# 6_AnalogChannels_5_6_7_8.net
KiCad netlist of a schematic drawn in Altium Designer
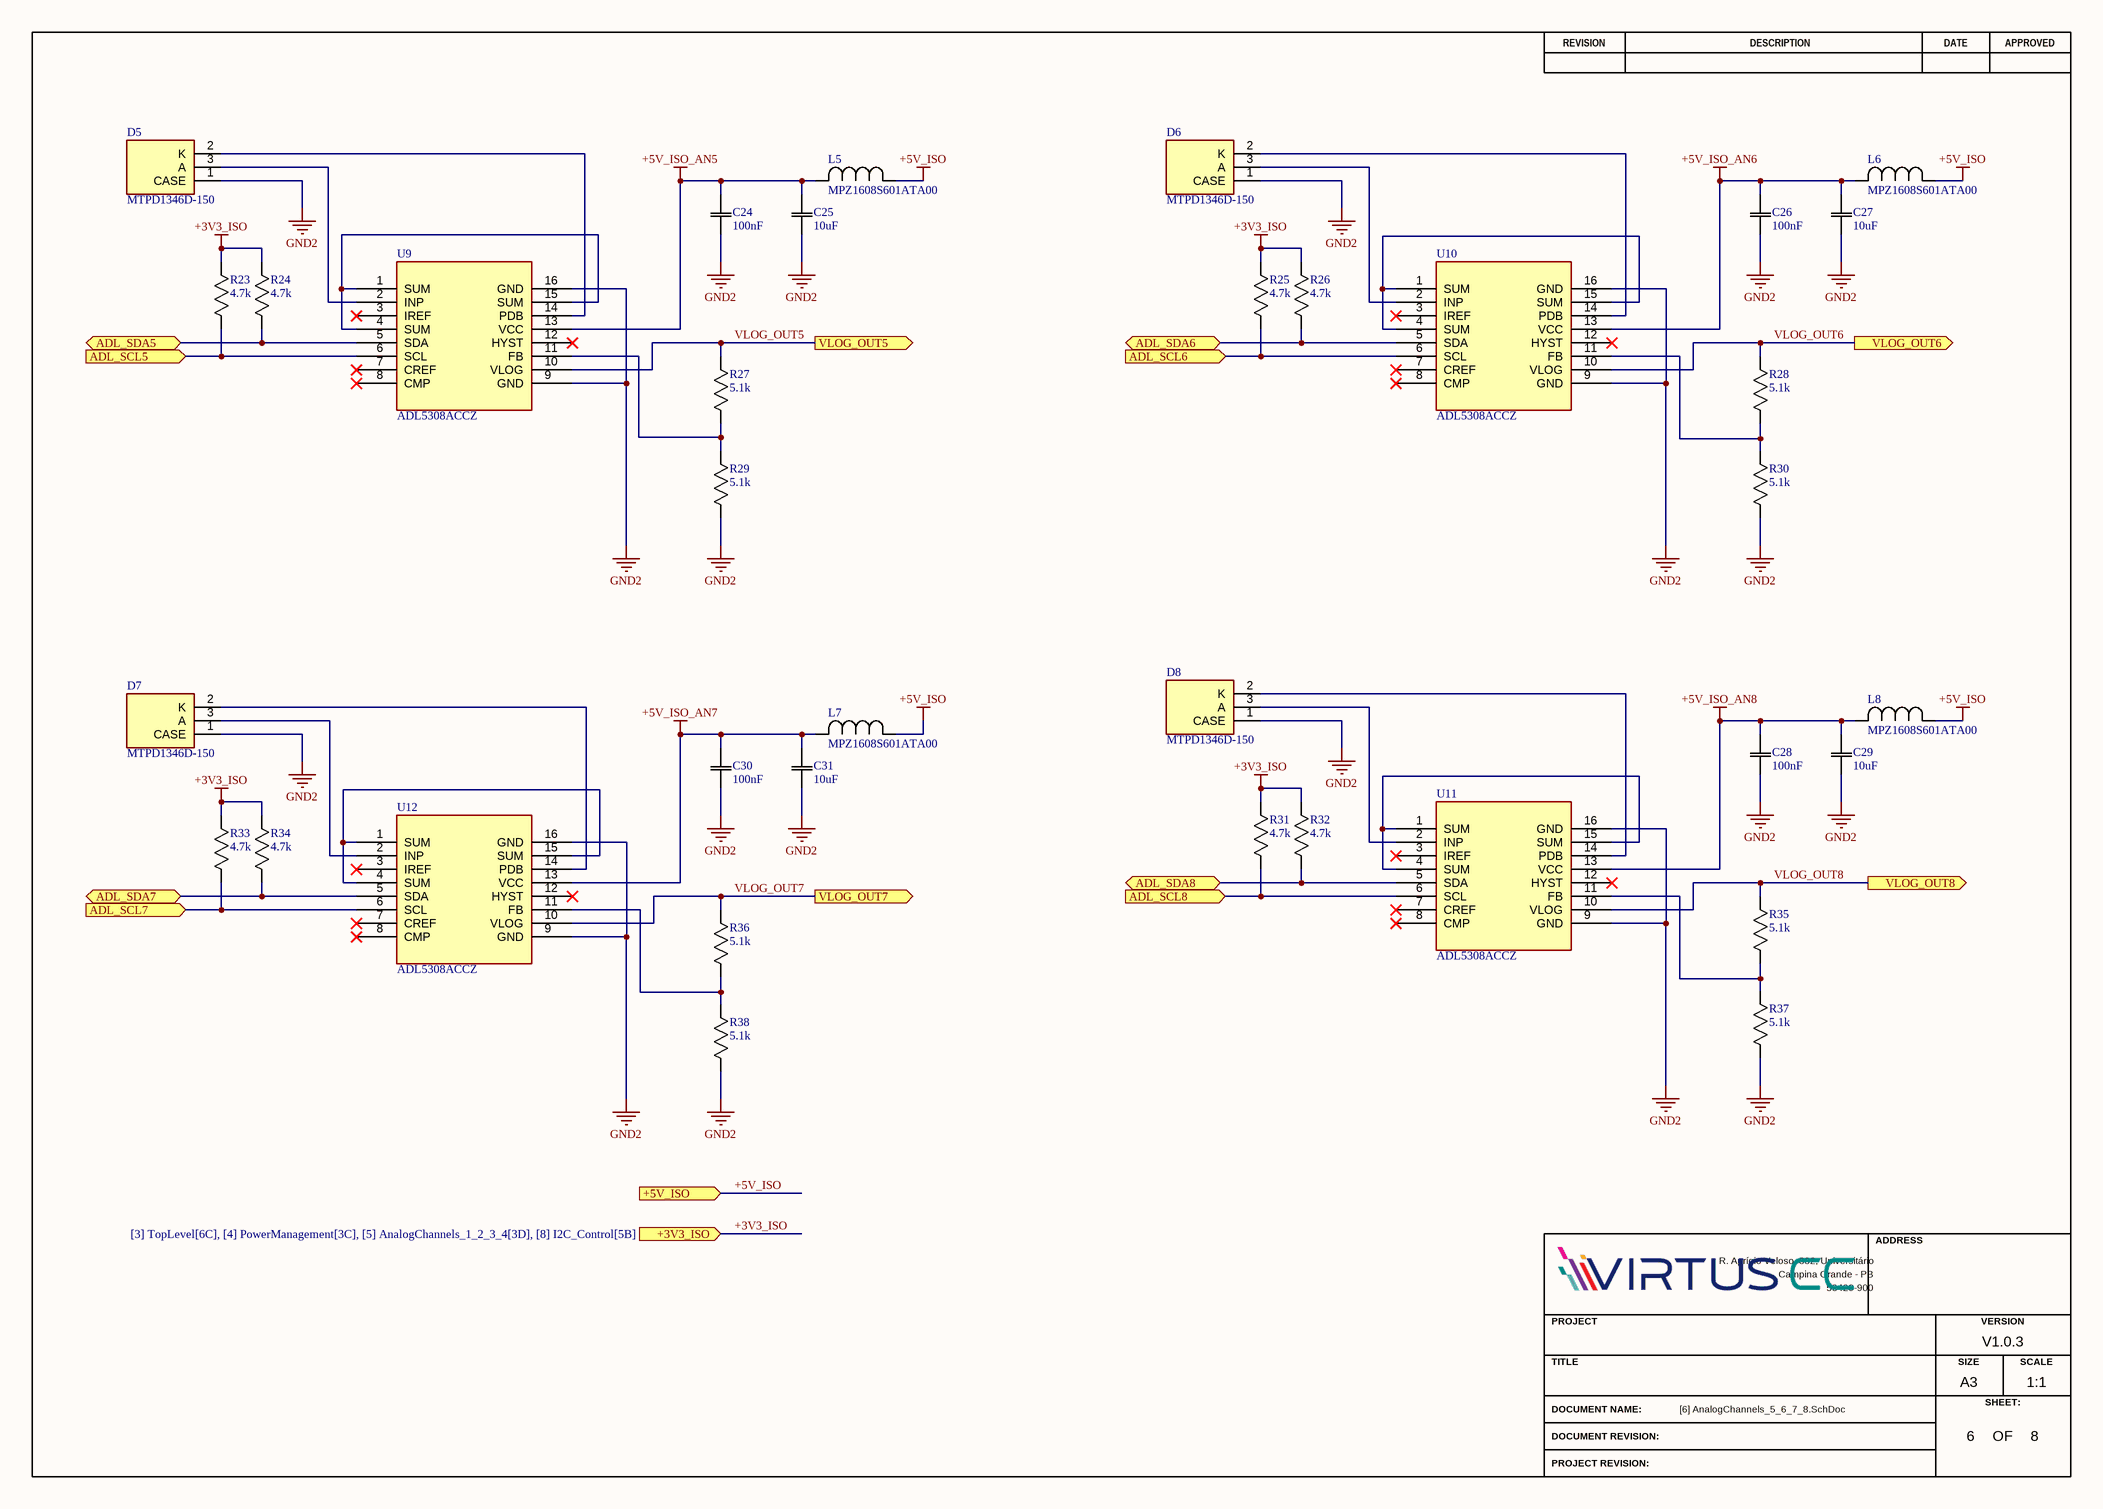
[diagram p0: [6] AnalogChannels_5_6_7_8.SchDoc]

(export (version "E")
  (design (tool "Eeschema 10.0.6"))
  (components
    (comp (ref "C24")
      (value "100nF")
      (footprint "CAPC1005X40N")
      (description "0.1 µF ±10% 50V Ceramic Capacitor X7R 0402 (1005 Metric)")
      (fields
        (field (name "MANUFACTURER_PART_NUMBER") "GCM155R71H104KE02D")
        (field (name "COPYRIGHT") "Copyright (C) 2026 Ultra Librarian. All rights reserved.")
      )
      (libsource (lib "PCEIOT") (part "GCM155R71H104KE02D"))
    )
    (comp (ref "C25")
      (value "10uF")
      (footprint "CAPC1005X40N")
      (description "10 µF ±20% 10V Ceramic Capacitor X5R 0402 (1005 Metric)")
      (fields
        (field (name "MANUFACTURER_PART_NUMBER") "GRT155R61A106ME13D")
        (field (name "COPYRIGHT") "Copyright (C) 2026 Ultra Librarian. All rights reserved.")
      )
      (libsource (lib "PCEIOT") (part "GRT155R61A106ME13D"))
    )
    (comp (ref "C26")
      (value "100nF")
      (footprint "CAPC1005X40N")
      (description "0.1 µF ±10% 50V Ceramic Capacitor X7R 0402 (1005 Metric)")
      (fields
        (field (name "MANUFACTURER_PART_NUMBER") "GCM155R71H104KE02D")
        (field (name "COPYRIGHT") "Copyright (C) 2026 Ultra Librarian. All rights reserved.")
      )
      (libsource (lib "PCEIOT") (part "GCM155R71H104KE02D"))
    )
    (comp (ref "C27")
      (value "10uF")
      (footprint "CAPC1005X40N")
      (description "10 µF ±20% 10V Ceramic Capacitor X5R 0402 (1005 Metric)")
      (fields
        (field (name "MANUFACTURER_PART_NUMBER") "GRT155R61A106ME13D")
        (field (name "COPYRIGHT") "Copyright (C) 2026 Ultra Librarian. All rights reserved.")
      )
      (libsource (lib "PCEIOT") (part "GRT155R61A106ME13D"))
    )
    (comp (ref "C28")
      (value "100nF")
      (footprint "CAPC1005X40N")
      (description "0.1 µF ±10% 50V Ceramic Capacitor X7R 0402 (1005 Metric)")
      (fields
        (field (name "MANUFACTURER_PART_NUMBER") "GCM155R71H104KE02D")
        (field (name "COPYRIGHT") "Copyright (C) 2026 Ultra Librarian. All rights reserved.")
      )
      (libsource (lib "PCEIOT") (part "GCM155R71H104KE02D"))
    )
    (comp (ref "C29")
      (value "10uF")
      (footprint "CAPC1005X40N")
      (description "10 µF ±20% 10V Ceramic Capacitor X5R 0402 (1005 Metric)")
      (fields
        (field (name "MANUFACTURER_PART_NUMBER") "GRT155R61A106ME13D")
        (field (name "COPYRIGHT") "Copyright (C) 2026 Ultra Librarian. All rights reserved.")
      )
      (libsource (lib "PCEIOT") (part "GRT155R61A106ME13D"))
    )
    (comp (ref "C30")
      (value "100nF")
      (footprint "CAPC1005X40N")
      (description "0.1 µF ±10% 50V Ceramic Capacitor X7R 0402 (1005 Metric)")
      (fields
        (field (name "MANUFACTURER_PART_NUMBER") "GCM155R71H104KE02D")
        (field (name "COPYRIGHT") "Copyright (C) 2026 Ultra Librarian. All rights reserved.")
      )
      (libsource (lib "PCEIOT") (part "GCM155R71H104KE02D"))
    )
    (comp (ref "C31")
      (value "10uF")
      (footprint "CAPC1005X40N")
      (description "10 µF ±20% 10V Ceramic Capacitor X5R 0402 (1005 Metric)")
      (fields
        (field (name "MANUFACTURER_PART_NUMBER") "GRT155R61A106ME13D")
        (field (name "COPYRIGHT") "Copyright (C) 2026 Ultra Librarian. All rights reserved.")
      )
      (libsource (lib "PCEIOT") (part "GRT155R61A106ME13D"))
    )
    (comp (ref "D5")
      (value "MTPD1346D-150")
      (footprint "TO127P540X1680-3N")
      (description "Photodiode 1300nm TO-46-3 Lens Top Metal Can")
      (libsource (lib "PCEIOT") (part "MTPD1346D-150"))
    )
    (comp (ref "D6")
      (value "MTPD1346D-150")
      (footprint "TO127P540X1680-3N")
      (description "Photodiode 1300nm TO-46-3 Lens Top Metal Can")
      (libsource (lib "PCEIOT") (part "MTPD1346D-150"))
    )
    (comp (ref "D7")
      (value "MTPD1346D-150")
      (footprint "TO127P540X1680-3N")
      (description "Photodiode 1300nm TO-46-3 Lens Top Metal Can")
      (libsource (lib "PCEIOT") (part "MTPD1346D-150"))
    )
    (comp (ref "D8")
      (value "MTPD1346D-150")
      (footprint "TO127P540X1680-3N")
      (description "Photodiode 1300nm TO-46-3 Lens Top Metal Can")
      (libsource (lib "PCEIOT") (part "MTPD1346D-150"))
    )
    (comp (ref "L5")
      (value "MPZ1608S601ATA00")
      (footprint "INDC1608X06N")
      (description "INDUCTOR; SMT (0603); FERRITE-BEAD; 600; TOL=+/-25%; 1A; -55 DEGC TO +125 DEGC")
      (fields (field (name "COPYRIGHT") "Copyright (C) 2026 Ultra Librarian. All rights reserved."))
      (libsource (lib "PCEIOT") (part "MPZ1608S601ATA00"))
    )
    (comp (ref "L6")
      (value "MPZ1608S601ATA00")
      (footprint "INDC1608X06N")
      (description "INDUCTOR; SMT (0603); FERRITE-BEAD; 600; TOL=+/-25%; 1A; -55 DEGC TO +125 DEGC")
      (fields (field (name "COPYRIGHT") "Copyright (C) 2026 Ultra Librarian. All rights reserved."))
      (libsource (lib "PCEIOT") (part "MPZ1608S601ATA00"))
    )
    (comp (ref "L7")
      (value "MPZ1608S601ATA00")
      (footprint "INDC1608X06N")
      (description "INDUCTOR; SMT (0603); FERRITE-BEAD; 600; TOL=+/-25%; 1A; -55 DEGC TO +125 DEGC")
      (fields (field (name "COPYRIGHT") "Copyright (C) 2026 Ultra Librarian. All rights reserved."))
      (libsource (lib "PCEIOT") (part "MPZ1608S601ATA00"))
    )
    (comp (ref "L8")
      (value "MPZ1608S601ATA00")
      (footprint "INDC1608X06N")
      (description "INDUCTOR; SMT (0603); FERRITE-BEAD; 600; TOL=+/-25%; 1A; -55 DEGC TO +125 DEGC")
      (fields (field (name "COPYRIGHT") "Copyright (C) 2026 Ultra Librarian. All rights reserved."))
      (libsource (lib "PCEIOT") (part "MPZ1608S601ATA00"))
    )
    (comp (ref "R23")
      (value "4.7k")
      (footprint "RESC1005X40N")
      (description "4.7 kOhms ±1% 0.063W, 1/16W Chip Resistor 0402 (1005 Metric) Moisture Resistant Thick Film")
      (fields
        (field (name "MANUFACTURER_PART_NUMBER") "RC0402FR-074K7L")
        (field (name "COPYRIGHT") "Copyright (C) 2025 Ultra Librarian. All rights reserved.")
      )
      (libsource (lib "PCEIOT") (part "RC0402FR-074K7L"))
    )
    (comp (ref "R24")
      (value "4.7k")
      (footprint "RESC1005X40N")
      (description "4.7 kOhms ±1% 0.063W, 1/16W Chip Resistor 0402 (1005 Metric) Moisture Resistant Thick Film")
      (fields
        (field (name "MANUFACTURER_PART_NUMBER") "RC0402FR-074K7L")
        (field (name "COPYRIGHT") "Copyright (C) 2025 Ultra Librarian. All rights reserved.")
      )
      (libsource (lib "PCEIOT") (part "RC0402FR-074K7L"))
    )
    (comp (ref "R25")
      (value "4.7k")
      (footprint "RESC1005X40N")
      (description "4.7 kOhms ±1% 0.063W, 1/16W Chip Resistor 0402 (1005 Metric) Moisture Resistant Thick Film")
      (fields
        (field (name "MANUFACTURER_PART_NUMBER") "RC0402FR-074K7L")
        (field (name "COPYRIGHT") "Copyright (C) 2025 Ultra Librarian. All rights reserved.")
      )
      (libsource (lib "PCEIOT") (part "RC0402FR-074K7L"))
    )
    (comp (ref "R26")
      (value "4.7k")
      (footprint "RESC1005X40N")
      (description "4.7 kOhms ±1% 0.063W, 1/16W Chip Resistor 0402 (1005 Metric) Moisture Resistant Thick Film")
      (fields
        (field (name "MANUFACTURER_PART_NUMBER") "RC0402FR-074K7L")
        (field (name "COPYRIGHT") "Copyright (C) 2025 Ultra Librarian. All rights reserved.")
      )
      (libsource (lib "PCEIOT") (part "RC0402FR-074K7L"))
    )
    (comp (ref "R27")
      (value "5.1k")
      (footprint "RESC1005X40N")
      (description "5.1 kOhms ±1% 0.063W, 1/16W Chip Resistor 0402 (1005 Metric) Moisture Resistant Thick Film")
      (fields
        (field (name "MANUFACTURER_PART_NUMBER") "RC0402FR-075K1L")
        (field (name "COPYRIGHT") "Copyright (C) 2025 Ultra Librarian. All rights reserved.")
      )
      (libsource (lib "PCEIOT") (part "RC0402FR-075K1L"))
    )
    (comp (ref "R28")
      (value "5.1k")
      (footprint "RESC1005X40N")
      (description "5.1 kOhms ±1% 0.063W, 1/16W Chip Resistor 0402 (1005 Metric) Moisture Resistant Thick Film")
      (fields
        (field (name "MANUFACTURER_PART_NUMBER") "RC0402FR-075K1L")
        (field (name "COPYRIGHT") "Copyright (C) 2025 Ultra Librarian. All rights reserved.")
      )
      (libsource (lib "PCEIOT") (part "RC0402FR-075K1L"))
    )
    (comp (ref "R29")
      (value "5.1k")
      (footprint "RESC1005X40N")
      (description "5.1 kOhms ±1% 0.063W, 1/16W Chip Resistor 0402 (1005 Metric) Moisture Resistant Thick Film")
      (fields
        (field (name "MANUFACTURER_PART_NUMBER") "RC0402FR-075K1L")
        (field (name "COPYRIGHT") "Copyright (C) 2025 Ultra Librarian. All rights reserved.")
      )
      (libsource (lib "PCEIOT") (part "RC0402FR-075K1L"))
    )
    (comp (ref "R30")
      (value "5.1k")
      (footprint "RESC1005X40N")
      (description "5.1 kOhms ±1% 0.063W, 1/16W Chip Resistor 0402 (1005 Metric) Moisture Resistant Thick Film")
      (fields
        (field (name "MANUFACTURER_PART_NUMBER") "RC0402FR-075K1L")
        (field (name "COPYRIGHT") "Copyright (C) 2025 Ultra Librarian. All rights reserved.")
      )
      (libsource (lib "PCEIOT") (part "RC0402FR-075K1L"))
    )
    (comp (ref "R31")
      (value "4.7k")
      (footprint "RESC1005X40N")
      (description "4.7 kOhms ±1% 0.063W, 1/16W Chip Resistor 0402 (1005 Metric) Moisture Resistant Thick Film")
      (fields
        (field (name "MANUFACTURER_PART_NUMBER") "RC0402FR-074K7L")
        (field (name "COPYRIGHT") "Copyright (C) 2025 Ultra Librarian. All rights reserved.")
      )
      (libsource (lib "PCEIOT") (part "RC0402FR-074K7L"))
    )
    (comp (ref "R32")
      (value "4.7k")
      (footprint "RESC1005X40N")
      (description "4.7 kOhms ±1% 0.063W, 1/16W Chip Resistor 0402 (1005 Metric) Moisture Resistant Thick Film")
      (fields
        (field (name "MANUFACTURER_PART_NUMBER") "RC0402FR-074K7L")
        (field (name "COPYRIGHT") "Copyright (C) 2025 Ultra Librarian. All rights reserved.")
      )
      (libsource (lib "PCEIOT") (part "RC0402FR-074K7L"))
    )
    (comp (ref "R33")
      (value "4.7k")
      (footprint "RESC1005X40N")
      (description "4.7 kOhms ±1% 0.063W, 1/16W Chip Resistor 0402 (1005 Metric) Moisture Resistant Thick Film")
      (fields
        (field (name "MANUFACTURER_PART_NUMBER") "RC0402FR-074K7L")
        (field (name "COPYRIGHT") "Copyright (C) 2025 Ultra Librarian. All rights reserved.")
      )
      (libsource (lib "PCEIOT") (part "RC0402FR-074K7L"))
    )
    (comp (ref "R34")
      (value "4.7k")
      (footprint "RESC1005X40N")
      (description "4.7 kOhms ±1% 0.063W, 1/16W Chip Resistor 0402 (1005 Metric) Moisture Resistant Thick Film")
      (fields
        (field (name "MANUFACTURER_PART_NUMBER") "RC0402FR-074K7L")
        (field (name "COPYRIGHT") "Copyright (C) 2025 Ultra Librarian. All rights reserved.")
      )
      (libsource (lib "PCEIOT") (part "RC0402FR-074K7L"))
    )
    (comp (ref "R35")
      (value "5.1k")
      (footprint "RESC1005X40N")
      (description "5.1 kOhms ±1% 0.063W, 1/16W Chip Resistor 0402 (1005 Metric) Moisture Resistant Thick Film")
      (fields
        (field (name "MANUFACTURER_PART_NUMBER") "RC0402FR-075K1L")
        (field (name "COPYRIGHT") "Copyright (C) 2025 Ultra Librarian. All rights reserved.")
      )
      (libsource (lib "PCEIOT") (part "RC0402FR-075K1L"))
    )
    (comp (ref "R36")
      (value "5.1k")
      (footprint "RESC1005X40N")
      (description "5.1 kOhms ±1% 0.063W, 1/16W Chip Resistor 0402 (1005 Metric) Moisture Resistant Thick Film")
      (fields
        (field (name "MANUFACTURER_PART_NUMBER") "RC0402FR-075K1L")
        (field (name "COPYRIGHT") "Copyright (C) 2025 Ultra Librarian. All rights reserved.")
      )
      (libsource (lib "PCEIOT") (part "RC0402FR-075K1L"))
    )
    (comp (ref "R37")
      (value "5.1k")
      (footprint "RESC1005X40N")
      (description "5.1 kOhms ±1% 0.063W, 1/16W Chip Resistor 0402 (1005 Metric) Moisture Resistant Thick Film")
      (fields
        (field (name "MANUFACTURER_PART_NUMBER") "RC0402FR-075K1L")
        (field (name "COPYRIGHT") "Copyright (C) 2025 Ultra Librarian. All rights reserved.")
      )
      (libsource (lib "PCEIOT") (part "RC0402FR-075K1L"))
    )
    (comp (ref "R38")
      (value "5.1k")
      (footprint "RESC1005X40N")
      (description "5.1 kOhms ±1% 0.063W, 1/16W Chip Resistor 0402 (1005 Metric) Moisture Resistant Thick Film")
      (fields
        (field (name "MANUFACTURER_PART_NUMBER") "RC0402FR-075K1L")
        (field (name "COPYRIGHT") "Copyright (C) 2025 Ultra Librarian. All rights reserved.")
      )
      (libsource (lib "PCEIOT") (part "RC0402FR-075K1L"))
    )
    (comp (ref "U9")
      (value "ADL5308ACCZ")
      (footprint "CC-14-4_ADI")
      (description "Logarithmic Converter, 105Deg C, Lga-Ep Rohs Compliant: Yes ¦Analog Devices, Inc. ADL5308ACCZ")
      (libsource (lib "PCEIOT") (part "ADL5308ACCZ"))
    )
    (comp (ref "U10")
      (value "ADL5308ACCZ")
      (footprint "CC-14-4_ADI")
      (description "Logarithmic Converter, 105Deg C, Lga-Ep Rohs Compliant: Yes ¦Analog Devices, Inc. ADL5308ACCZ")
      (libsource (lib "PCEIOT") (part "ADL5308ACCZ"))
    )
    (comp (ref "U11")
      (value "ADL5308ACCZ")
      (footprint "CC-14-4_ADI")
      (description "Logarithmic Converter, 105Deg C, Lga-Ep Rohs Compliant: Yes ¦Analog Devices, Inc. ADL5308ACCZ")
      (libsource (lib "PCEIOT") (part "ADL5308ACCZ"))
    )
    (comp (ref "U12")
      (value "ADL5308ACCZ")
      (footprint "CC-14-4_ADI")
      (description "Logarithmic Converter, 105Deg C, Lga-Ep Rohs Compliant: Yes ¦Analog Devices, Inc. ADL5308ACCZ")
      (libsource (lib "PCEIOT") (part "ADL5308ACCZ"))
    )
  )
  (nets
    (net (code "1") (name "+3V3_ISO") (class "Default")
      (node (ref "R23") (pin "1") (pinfunction "1_1") (pintype "passive"))
      (node (ref "R24") (pin "1") (pinfunction "1_1") (pintype "passive"))
      (node (ref "R25") (pin "1") (pinfunction "1_1") (pintype "passive"))
      (node (ref "R26") (pin "1") (pinfunction "1_1") (pintype "passive"))
      (node (ref "R31") (pin "1") (pinfunction "1_1") (pintype "passive"))
      (node (ref "R32") (pin "1") (pinfunction "1_1") (pintype "passive"))
      (node (ref "R33") (pin "1") (pinfunction "1_1") (pintype "passive"))
      (node (ref "R34") (pin "1") (pinfunction "1_1") (pintype "passive"))
    )
    (net (code "2") (name "+5V_ISO") (class "Default")
      (node (ref "L5") (pin "1") (pinfunction "1_1") (pintype "passive"))
      (node (ref "L6") (pin "1") (pinfunction "1_1") (pintype "passive"))
      (node (ref "L7") (pin "1") (pinfunction "1_1") (pintype "passive"))
      (node (ref "L8") (pin "1") (pinfunction "1_1") (pintype "passive"))
    )
    (net (code "3") (name "+5V_ISO_AN5") (class "Default")
      (node (ref "C24") (pin "2") (pinfunction "2_2") (pintype "passive"))
      (node (ref "C25") (pin "2") (pinfunction "2_2") (pintype "passive"))
      (node (ref "L5") (pin "2") (pinfunction "2_2") (pintype "passive"))
      (node (ref "U9") (pin "13") (pinfunction "VCC_13") (pintype "passive"))
    )
    (net (code "4") (name "+5V_ISO_AN6") (class "Default")
      (node (ref "C26") (pin "2") (pinfunction "2_2") (pintype "passive"))
      (node (ref "C27") (pin "2") (pinfunction "2_2") (pintype "passive"))
      (node (ref "L6") (pin "2") (pinfunction "2_2") (pintype "passive"))
      (node (ref "U10") (pin "13") (pinfunction "VCC_13") (pintype "passive"))
    )
    (net (code "5") (name "+5V_ISO_AN7") (class "Default")
      (node (ref "C30") (pin "2") (pinfunction "2_2") (pintype "passive"))
      (node (ref "C31") (pin "2") (pinfunction "2_2") (pintype "passive"))
      (node (ref "L7") (pin "2") (pinfunction "2_2") (pintype "passive"))
      (node (ref "U12") (pin "13") (pinfunction "VCC_13") (pintype "passive"))
    )
    (net (code "6") (name "+5V_ISO_AN8") (class "Default")
      (node (ref "C28") (pin "2") (pinfunction "2_2") (pintype "passive"))
      (node (ref "C29") (pin "2") (pinfunction "2_2") (pintype "passive"))
      (node (ref "L8") (pin "2") (pinfunction "2_2") (pintype "passive"))
      (node (ref "U11") (pin "13") (pinfunction "VCC_13") (pintype "passive"))
    )
    (net (code "7") (name "/ADL_SCL5") (class "Default")
      (node (ref "R23") (pin "2") (pinfunction "2_2") (pintype "passive"))
      (node (ref "U9") (pin "6") (pinfunction "SCL_6") (pintype "passive"))
    )
    (net (code "8") (name "/ADL_SCL6") (class "Default")
      (node (ref "R25") (pin "2") (pinfunction "2_2") (pintype "passive"))
      (node (ref "U10") (pin "6") (pinfunction "SCL_6") (pintype "passive"))
    )
    (net (code "9") (name "/ADL_SCL7") (class "Default")
      (node (ref "R33") (pin "2") (pinfunction "2_2") (pintype "passive"))
      (node (ref "U12") (pin "6") (pinfunction "SCL_6") (pintype "passive"))
    )
    (net (code "10") (name "/ADL_SCL8") (class "Default")
      (node (ref "R31") (pin "2") (pinfunction "2_2") (pintype "passive"))
      (node (ref "U11") (pin "6") (pinfunction "SCL_6") (pintype "passive"))
    )
    (net (code "11") (name "/ADL_SDA5") (class "Default")
      (node (ref "R24") (pin "2") (pinfunction "2_2") (pintype "passive"))
      (node (ref "U9") (pin "5") (pinfunction "SDA_5") (pintype "passive"))
    )
    (net (code "12") (name "/ADL_SDA6") (class "Default")
      (node (ref "R26") (pin "2") (pinfunction "2_2") (pintype "passive"))
      (node (ref "U10") (pin "5") (pinfunction "SDA_5") (pintype "passive"))
    )
    (net (code "13") (name "/ADL_SDA7") (class "Default")
      (node (ref "R34") (pin "2") (pinfunction "2_2") (pintype "passive"))
      (node (ref "U12") (pin "5") (pinfunction "SDA_5") (pintype "passive"))
    )
    (net (code "14") (name "/ADL_SDA8") (class "Default")
      (node (ref "R32") (pin "2") (pinfunction "2_2") (pintype "passive"))
      (node (ref "U11") (pin "5") (pinfunction "SDA_5") (pintype "passive"))
    )
    (net (code "15") (name "/VLOG_OUT5") (class "Default")
      (node (ref "R27") (pin "1") (pinfunction "1_1") (pintype "passive"))
      (node (ref "U9") (pin "10") (pinfunction "VLOG_10") (pintype "passive"))
    )
    (net (code "16") (name "/VLOG_OUT6") (class "Default")
      (node (ref "R28") (pin "1") (pinfunction "1_1") (pintype "passive"))
      (node (ref "U10") (pin "10") (pinfunction "VLOG_10") (pintype "passive"))
    )
    (net (code "17") (name "/VLOG_OUT7") (class "Default")
      (node (ref "R36") (pin "1") (pinfunction "1_1") (pintype "passive"))
      (node (ref "U12") (pin "10") (pinfunction "VLOG_10") (pintype "passive"))
    )
    (net (code "18") (name "/VLOG_OUT8") (class "Default")
      (node (ref "R35") (pin "1") (pinfunction "1_1") (pintype "passive"))
      (node (ref "U11") (pin "10") (pinfunction "VLOG_10") (pintype "passive"))
    )
    (net (code "19") (name "GND2") (class "Default")
      (node (ref "C24") (pin "1") (pinfunction "1_1") (pintype "passive"))
      (node (ref "C25") (pin "1") (pinfunction "1_1") (pintype "passive"))
      (node (ref "C26") (pin "1") (pinfunction "1_1") (pintype "passive"))
      (node (ref "C27") (pin "1") (pinfunction "1_1") (pintype "passive"))
      (node (ref "C28") (pin "1") (pinfunction "1_1") (pintype "passive"))
      (node (ref "C29") (pin "1") (pinfunction "1_1") (pintype "passive"))
      (node (ref "C30") (pin "1") (pinfunction "1_1") (pintype "passive"))
      (node (ref "C31") (pin "1") (pinfunction "1_1") (pintype "passive"))
      (node (ref "D5") (pin "1") (pinfunction "CASE_1") (pintype "passive"))
      (node (ref "D6") (pin "1") (pinfunction "CASE_1") (pintype "passive"))
      (node (ref "D7") (pin "1") (pinfunction "CASE_1") (pintype "passive"))
      (node (ref "D8") (pin "1") (pinfunction "CASE_1") (pintype "passive"))
      (node (ref "R29") (pin "2") (pinfunction "2_2") (pintype "passive"))
      (node (ref "R30") (pin "2") (pinfunction "2_2") (pintype "passive"))
      (node (ref "R37") (pin "2") (pinfunction "2_2") (pintype "passive"))
      (node (ref "R38") (pin "2") (pinfunction "2_2") (pintype "passive"))
      (node (ref "U10") (pin "16") (pinfunction "GND_16") (pintype "passive"))
      (node (ref "U10") (pin "9") (pinfunction "GND_9") (pintype "passive"))
      (node (ref "U11") (pin "16") (pinfunction "GND_16") (pintype "passive"))
      (node (ref "U11") (pin "9") (pinfunction "GND_9") (pintype "passive"))
      (node (ref "U12") (pin "16") (pinfunction "GND_16") (pintype "passive"))
      (node (ref "U12") (pin "9") (pinfunction "GND_9") (pintype "passive"))
      (node (ref "U9") (pin "16") (pinfunction "GND_16") (pintype "passive"))
      (node (ref "U9") (pin "9") (pinfunction "GND_9") (pintype "passive"))
    )
    (net (code "20") (name "Net-(D5-A)") (class "Default")
      (node (ref "D5") (pin "3") (pinfunction "A_3") (pintype "passive"))
      (node (ref "U9") (pin "2") (pinfunction "INP_2") (pintype "passive"))
    )
    (net (code "21") (name "Net-(D5-K)") (class "Default")
      (node (ref "D5") (pin "2") (pinfunction "K_2") (pintype "passive"))
      (node (ref "U9") (pin "14") (pinfunction "PDB_14") (pintype "passive"))
    )
    (net (code "22") (name "Net-(D6-A)") (class "Default")
      (node (ref "D6") (pin "3") (pinfunction "A_3") (pintype "passive"))
      (node (ref "U10") (pin "2") (pinfunction "INP_2") (pintype "passive"))
    )
    (net (code "23") (name "Net-(D6-K)") (class "Default")
      (node (ref "D6") (pin "2") (pinfunction "K_2") (pintype "passive"))
      (node (ref "U10") (pin "14") (pinfunction "PDB_14") (pintype "passive"))
    )
    (net (code "24") (name "Net-(D7-A)") (class "Default")
      (node (ref "D7") (pin "3") (pinfunction "A_3") (pintype "passive"))
      (node (ref "U12") (pin "2") (pinfunction "INP_2") (pintype "passive"))
    )
    (net (code "25") (name "Net-(D7-K)") (class "Default")
      (node (ref "D7") (pin "2") (pinfunction "K_2") (pintype "passive"))
      (node (ref "U12") (pin "14") (pinfunction "PDB_14") (pintype "passive"))
    )
    (net (code "26") (name "Net-(D8-A)") (class "Default")
      (node (ref "D8") (pin "3") (pinfunction "A_3") (pintype "passive"))
      (node (ref "U11") (pin "2") (pinfunction "INP_2") (pintype "passive"))
    )
    (net (code "27") (name "Net-(D8-K)") (class "Default")
      (node (ref "D8") (pin "2") (pinfunction "K_2") (pintype "passive"))
      (node (ref "U11") (pin "14") (pinfunction "PDB_14") (pintype "passive"))
    )
    (net (code "28") (name "Net-(U9-FB)") (class "Default")
      (node (ref "R27") (pin "2") (pinfunction "2_2") (pintype "passive"))
      (node (ref "R29") (pin "1") (pinfunction "1_1") (pintype "passive"))
      (node (ref "U9") (pin "11") (pinfunction "FB_11") (pintype "passive"))
    )
    (net (code "29") (name "Net-(U9-SUM-Pad1)") (class "Default")
      (node (ref "U9") (pin "1") (pinfunction "SUM_1") (pintype "passive"))
      (node (ref "U9") (pin "15") (pinfunction "SUM_15") (pintype "passive"))
      (node (ref "U9") (pin "4") (pinfunction "SUM_4") (pintype "passive"))
    )
    (net (code "30") (name "Net-(U10-FB)") (class "Default")
      (node (ref "R28") (pin "2") (pinfunction "2_2") (pintype "passive"))
      (node (ref "R30") (pin "1") (pinfunction "1_1") (pintype "passive"))
      (node (ref "U10") (pin "11") (pinfunction "FB_11") (pintype "passive"))
    )
    (net (code "31") (name "Net-(U10-SUM-Pad1)") (class "Default")
      (node (ref "U10") (pin "1") (pinfunction "SUM_1") (pintype "passive"))
      (node (ref "U10") (pin "15") (pinfunction "SUM_15") (pintype "passive"))
      (node (ref "U10") (pin "4") (pinfunction "SUM_4") (pintype "passive"))
    )
    (net (code "32") (name "Net-(U11-FB)") (class "Default")
      (node (ref "R35") (pin "2") (pinfunction "2_2") (pintype "passive"))
      (node (ref "R37") (pin "1") (pinfunction "1_1") (pintype "passive"))
      (node (ref "U11") (pin "11") (pinfunction "FB_11") (pintype "passive"))
    )
    (net (code "33") (name "Net-(U11-SUM-Pad1)") (class "Default")
      (node (ref "U11") (pin "1") (pinfunction "SUM_1") (pintype "passive"))
      (node (ref "U11") (pin "15") (pinfunction "SUM_15") (pintype "passive"))
      (node (ref "U11") (pin "4") (pinfunction "SUM_4") (pintype "passive"))
    )
    (net (code "34") (name "Net-(U12-FB)") (class "Default")
      (node (ref "R36") (pin "2") (pinfunction "2_2") (pintype "passive"))
      (node (ref "R38") (pin "1") (pinfunction "1_1") (pintype "passive"))
      (node (ref "U12") (pin "11") (pinfunction "FB_11") (pintype "passive"))
    )
    (net (code "35") (name "Net-(U12-SUM-Pad1)") (class "Default")
      (node (ref "U12") (pin "1") (pinfunction "SUM_1") (pintype "passive"))
      (node (ref "U12") (pin "15") (pinfunction "SUM_15") (pintype "passive"))
      (node (ref "U12") (pin "4") (pinfunction "SUM_4") (pintype "passive"))
    )
    (net (code "36") (name "unconnected-(U9-CMP-Pad8)") (class "Default")
      (node (ref "U9") (pin "8") (pinfunction "CMP_8") (pintype "passive+no_connect"))
    )
    (net (code "37") (name "unconnected-(U9-CREF-Pad7)") (class "Default")
      (node (ref "U9") (pin "7") (pinfunction "CREF_7") (pintype "passive+no_connect"))
    )
    (net (code "38") (name "unconnected-(U9-HYST-Pad12)") (class "Default")
      (node (ref "U9") (pin "12") (pinfunction "HYST_12") (pintype "passive+no_connect"))
    )
    (net (code "39") (name "unconnected-(U9-IREF-Pad3)") (class "Default")
      (node (ref "U9") (pin "3") (pinfunction "IREF_3") (pintype "passive+no_connect"))
    )
    (net (code "40") (name "unconnected-(U10-CMP-Pad8)") (class "Default")
      (node (ref "U10") (pin "8") (pinfunction "CMP_8") (pintype "passive+no_connect"))
    )
    (net (code "41") (name "unconnected-(U10-CREF-Pad7)") (class "Default")
      (node (ref "U10") (pin "7") (pinfunction "CREF_7") (pintype "passive+no_connect"))
    )
    (net (code "42") (name "unconnected-(U10-HYST-Pad12)") (class "Default")
      (node (ref "U10") (pin "12") (pinfunction "HYST_12") (pintype "passive+no_connect"))
    )
    (net (code "43") (name "unconnected-(U10-IREF-Pad3)") (class "Default")
      (node (ref "U10") (pin "3") (pinfunction "IREF_3") (pintype "passive+no_connect"))
    )
    (net (code "44") (name "unconnected-(U11-CMP-Pad8)") (class "Default")
      (node (ref "U11") (pin "8") (pinfunction "CMP_8") (pintype "passive+no_connect"))
    )
    (net (code "45") (name "unconnected-(U11-CREF-Pad7)") (class "Default")
      (node (ref "U11") (pin "7") (pinfunction "CREF_7") (pintype "passive+no_connect"))
    )
    (net (code "46") (name "unconnected-(U11-HYST-Pad12)") (class "Default")
      (node (ref "U11") (pin "12") (pinfunction "HYST_12") (pintype "passive+no_connect"))
    )
    (net (code "47") (name "unconnected-(U11-IREF-Pad3)") (class "Default")
      (node (ref "U11") (pin "3") (pinfunction "IREF_3") (pintype "passive+no_connect"))
    )
    (net (code "48") (name "unconnected-(U12-CMP-Pad8)") (class "Default")
      (node (ref "U12") (pin "8") (pinfunction "CMP_8") (pintype "passive+no_connect"))
    )
    (net (code "49") (name "unconnected-(U12-CREF-Pad7)") (class "Default")
      (node (ref "U12") (pin "7") (pinfunction "CREF_7") (pintype "passive+no_connect"))
    )
    (net (code "50") (name "unconnected-(U12-HYST-Pad12)") (class "Default")
      (node (ref "U12") (pin "12") (pinfunction "HYST_12") (pintype "passive+no_connect"))
    )
    (net (code "51") (name "unconnected-(U12-IREF-Pad3)") (class "Default")
      (node (ref "U12") (pin "3") (pinfunction "IREF_3") (pintype "passive+no_connect"))
    )
  )
)
